# v0_4v1_0.net
KiCad netlist of a schematic drawn in EAGLE
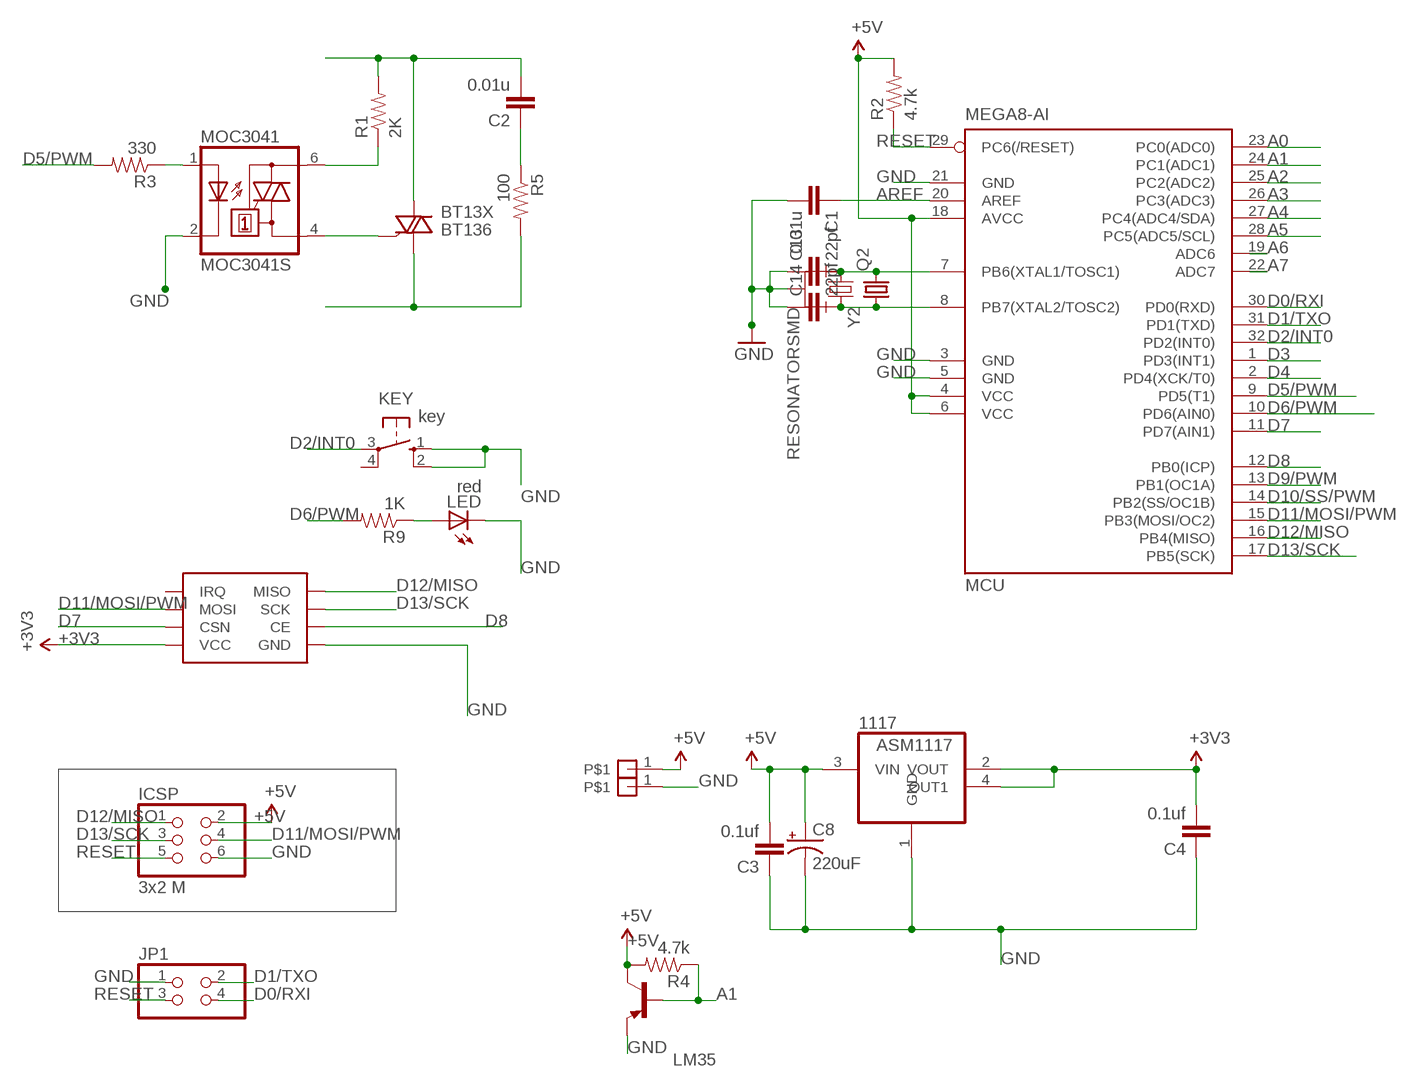
[diagram p0: schematic, sheet 1]

(export (version "E")
  (design (tool "Eeschema 10.0.6"))
  (components
    (comp (ref "1117")
      (value "ASM1117")
      (footprint "eagle-import:SOT223")
      (fields (field (name "MPN") "REG1117"))
      (libsource (lib "eagle-import") (part "ASM1117"))
    )
    (comp (ref "BT13X")
      (value "BT136")
      (footprint "eagle-import:TO252")
      (libsource (lib "eagle-import") (part "BT136"))
    )
    (comp (ref "C1")
      (value "0.01u")
      (footprint "eagle-import:0603-CAP")
      (libsource (lib "eagle-import") (part "MY2_CAP0603-CAP"))
    )
    (comp (ref "C2")
      (value "0.01u")
      (footprint "eagle-import:C050-024X044")
      (libsource (lib "eagle-import") (part "C-EU050-024X044"))
    )
    (comp (ref "C3")
      (value "0.1uf")
      (footprint "eagle-import:0603-CAP")
      (libsource (lib "eagle-import") (part "MY_CAP0603-CAP"))
    )
    (comp (ref "C4")
      (value "0.1uf")
      (footprint "eagle-import:0603-CAP")
      (libsource (lib "eagle-import") (part "MY_CAP0603-CAP"))
    )
    (comp (ref "C8")
      (value "220uF")
      (footprint "eagle-import:EIA3528")
      (libsource (lib "eagle-import") (part "CAP_POL3528"))
    )
    (comp (ref "C13")
      (value "22pf")
      (footprint "eagle-import:0603-CAP")
      (libsource (lib "eagle-import") (part "CAP0603-CAP"))
    )
    (comp (ref "C14")
      (value "22pf")
      (footprint "eagle-import:0603-CAP")
      (libsource (lib "eagle-import") (part "CAP0603-CAP"))
    )
    (comp (ref "ICSP")
      (value "3x2 M")
      (footprint "eagle-import:2X03")
      (libsource (lib "eagle-import") (part "PINHD-2X3"))
    )
    (comp (ref "JP1")
      (value "PINHD-2X2")
      (footprint "eagle-import:2X02")
      (libsource (lib "eagle-import") (part "PINHD-2X2"))
    )
    (comp (ref "KEY")
      (value "key")
      (footprint "eagle-import:B3F-10XX")
      (fields
        (field (name "MPN") "B3F-1000")
        (field (name "MPN_1") "B3F-1000")
        (field (name "OC_FARNELL") "176432")
        (field (name "OC_NEWARK") "36M3542")
      )
      (libsource (lib "eagle-import") (part "10-XX"))
    )
    (comp (ref "LED")
      (value "red")
      (footprint "eagle-import:LED3MM")
      (libsource (lib "eagle-import") (part "LED3MM"))
    )
    (comp (ref "LM35")
      (value "-PNP-TO92-E1")
      (footprint "eagle-import:TO92-E1")
      (libsource (lib "eagle-import") (part "-PNP-TO92-E1"))
    )
    (comp (ref "MCU")
      (value "MEGA8-AI")
      (footprint "eagle-import:TQFP32-08")
      (fields (field (name "MPN") "ATMEGA8-16AU"))
      (libsource (lib "eagle-import") (part "MEGA8-AI"))
    )
    (comp (ref "MOC3041")
      (value "MOC3041S")
      (footprint "eagle-import:DIL6-SMD")
      (fields
        (field (name "MF") "FAIRCHILD SEMICONDUCTOR")
        (field (name "MPN") "MOC3041S-M")
        (field (name "MF_1") "FAIRCHILD SEMICONDUCTOR")
        (field (name "MPN_1") "MOC3041S-M")
        (field (name "OC_NEWARK") "05C2885")
      )
      (libsource (lib "eagle-import") (part "MOC30S41"))
    )
    (comp (ref "Q2")
      (value "CRYSTALHC49S")
      (footprint "eagle-import:HC49_S")
      (libsource (lib "eagle-import") (part "CRYSTALHC49S"))
    )
    (comp (ref "R1")
      (value "2K")
      (footprint "eagle-import:AXIAL-0.3")
      (libsource (lib "eagle-import") (part "MY3_RESISTORPTH1"))
    )
    (comp (ref "R2")
      (value "4.7k")
      (footprint "eagle-import:0603-RES")
      (libsource (lib "eagle-import") (part "RESISTOR0603-RES"))
    )
    (comp (ref "R3")
      (value "330")
      (footprint "eagle-import:0603-RES")
      (libsource (lib "eagle-import") (part "RESISTOR0603-RES"))
    )
    (comp (ref "R4")
      (value "4.7k")
      (footprint "eagle-import:0603-RES")
      (libsource (lib "eagle-import") (part "RESISTOR0603-RES"))
    )
    (comp (ref "R5")
      (value "100")
      (footprint "eagle-import:AXIAL-0.3")
      (libsource (lib "eagle-import") (part "MY3_RESISTORPTH1"))
    )
    (comp (ref "R9")
      (value "1K")
      (footprint "eagle-import:0603-RES")
      (libsource (lib "eagle-import") (part "RESISTOR0603-RES"))
    )
    (comp (ref "U$3")
      (value "PIN1")
      (footprint "eagle-import:PIN1")
      (libsource (lib "eagle-import") (part "PIN1"))
    )
    (comp (ref "U$4")
      (value "PIN1")
      (footprint "eagle-import:PIN1")
      (libsource (lib "eagle-import") (part "PIN1"))
    )
    (comp (ref "U$6")
      (value "NRF")
      (footprint "eagle-import:NRF")
      (libsource (lib "eagle-import") (part "NRF"))
    )
    (comp (ref "Y2")
      (value "RESONATORSMD")
      (footprint "eagle-import:RESONATOR-SMD")
      (libsource (lib "eagle-import") (part "RESONATORSMD"))
    )
  )
  (nets
    (net (code "1") (name "+3V3") (class "Default")
      (node (ref "1117") (pin "2") (pinfunction "VOUT_2") (pintype "output"))
      (node (ref "1117") (pin "4") (pinfunction "OUT1_4") (pintype "bidirectional"))
      (node (ref "C4") (pin "2") (pinfunction "2_2") (pintype "passive"))
      (node (ref "U$6") (pin "P$2") (pinfunction "VCC_P$2") (pintype "bidirectional"))
    )
    (net (code "2") (name "+5V") (class "Default")
      (node (ref "1117") (pin "3") (pinfunction "VIN_3") (pintype "input"))
      (node (ref "C3") (pin "2") (pinfunction "2_2") (pintype "passive"))
      (node (ref "C8") (pin "A") (pinfunction "+_A") (pintype "passive"))
      (node (ref "ICSP") (pin "2") (pinfunction "2_2") (pintype "passive"))
      (node (ref "LM35") (pin "1") (pinfunction "C_1") (pintype "passive"))
      (node (ref "MCU") (pin "18") (pinfunction "AVCC_18") (pintype "power_in"))
      (node (ref "MCU") (pin "4") (pinfunction "VCC_4") (pintype "power_in"))
      (node (ref "MCU") (pin "6") (pinfunction "VCC_6") (pintype "power_in"))
      (node (ref "R2") (pin "2") (pinfunction "2_2") (pintype "passive"))
      (node (ref "R4") (pin "2") (pinfunction "2_2") (pintype "passive"))
      (node (ref "U$3") (pin "1") (pinfunction "P$1_1") (pintype "bidirectional"))
    )
    (net (code "3") (name "/A0") (class "Default")
      (node (ref "MCU") (pin "23") (pinfunction "PC0(ADC0)_23") (pintype "bidirectional"))
    )
    (net (code "4") (name "/A1") (class "Default")
      (node (ref "LM35") (pin "2") (pinfunction "B_2") (pintype "passive"))
      (node (ref "MCU") (pin "24") (pinfunction "PC1(ADC1)_24") (pintype "bidirectional"))
      (node (ref "R4") (pin "1") (pinfunction "1_1") (pintype "passive"))
    )
    (net (code "5") (name "/A2") (class "Default")
      (node (ref "MCU") (pin "25") (pinfunction "PC2(ADC2)_25") (pintype "bidirectional"))
    )
    (net (code "6") (name "/A3") (class "Default")
      (node (ref "MCU") (pin "26") (pinfunction "PC3(ADC3)_26") (pintype "bidirectional"))
    )
    (net (code "7") (name "/A4") (class "Default")
      (node (ref "MCU") (pin "27") (pinfunction "PC4(ADC4/SDA)_27") (pintype "bidirectional"))
    )
    (net (code "8") (name "/A5") (class "Default")
      (node (ref "MCU") (pin "28") (pinfunction "PC5(ADC5/SCL)_28") (pintype "bidirectional"))
    )
    (net (code "9") (name "/A6") (class "Default")
      (node (ref "MCU") (pin "19") (pinfunction "ADC6_19") (pintype "bidirectional"))
    )
    (net (code "10") (name "/A7") (class "Default")
      (node (ref "MCU") (pin "22") (pinfunction "ADC7_22") (pintype "bidirectional"))
    )
    (net (code "11") (name "/AREF") (class "Default")
      (node (ref "C1") (pin "1") (pinfunction "1_1") (pintype "passive"))
      (node (ref "MCU") (pin "20") (pinfunction "AREF_20") (pintype "passive"))
    )
    (net (code "12") (name "/D0{slash}RXI") (class "Default")
      (node (ref "JP1") (pin "4") (pinfunction "4_4") (pintype "passive"))
      (node (ref "MCU") (pin "30") (pinfunction "PD0(RXD)_30") (pintype "bidirectional"))
    )
    (net (code "13") (name "/D1{slash}TXO") (class "Default")
      (node (ref "JP1") (pin "2") (pinfunction "2_2") (pintype "passive"))
      (node (ref "MCU") (pin "31") (pinfunction "PD1(TXD)_31") (pintype "bidirectional"))
    )
    (net (code "14") (name "/D2{slash}INT0") (class "Default")
      (node (ref "KEY") (pin "3") (pinfunction "P_3") (pintype "passive"))
      (node (ref "MCU") (pin "32") (pinfunction "PD2(INT0)_32") (pintype "bidirectional"))
    )
    (net (code "15") (name "/D3") (class "Default")
      (node (ref "MCU") (pin "1") (pinfunction "PD3(INT1)_1") (pintype "bidirectional"))
    )
    (net (code "16") (name "/D4") (class "Default")
      (node (ref "MCU") (pin "2") (pinfunction "PD4(XCK/T0)_2") (pintype "bidirectional"))
    )
    (net (code "17") (name "/D5{slash}PWM") (class "Default")
      (node (ref "MCU") (pin "9") (pinfunction "PD5(T1)_9") (pintype "bidirectional"))
      (node (ref "R3") (pin "2") (pinfunction "2_2") (pintype "passive"))
    )
    (net (code "18") (name "/D6{slash}PWM") (class "Default")
      (node (ref "MCU") (pin "10") (pinfunction "PD6(AIN0)_10") (pintype "bidirectional"))
      (node (ref "R9") (pin "2") (pinfunction "2_2") (pintype "passive"))
    )
    (net (code "19") (name "/D7") (class "Default")
      (node (ref "MCU") (pin "11") (pinfunction "PD7(AIN1)_11") (pintype "bidirectional"))
      (node (ref "U$6") (pin "P$4") (pinfunction "CSN_P$4") (pintype "bidirectional"))
    )
    (net (code "20") (name "/D8") (class "Default")
      (node (ref "MCU") (pin "12") (pinfunction "PB0(ICP)_12") (pintype "bidirectional"))
      (node (ref "U$6") (pin "P$3") (pinfunction "CE_P$3") (pintype "bidirectional"))
    )
    (net (code "21") (name "/D9{slash}PWM") (class "Default")
      (node (ref "MCU") (pin "13") (pinfunction "PB1(OC1A)_13") (pintype "bidirectional"))
    )
    (net (code "22") (name "/D10{slash}SS{slash}PWM") (class "Default")
      (node (ref "MCU") (pin "14") (pinfunction "PB2(SS/OC1B)_14") (pintype "bidirectional"))
    )
    (net (code "23") (name "/D11{slash}MOSI{slash}PWM") (class "Default")
      (node (ref "ICSP") (pin "4") (pinfunction "4_4") (pintype "passive"))
      (node (ref "MCU") (pin "15") (pinfunction "PB3(MOSI/OC2)_15") (pintype "bidirectional"))
      (node (ref "U$6") (pin "P$6") (pinfunction "MOSI_P$6") (pintype "bidirectional"))
    )
    (net (code "24") (name "/D12{slash}MISO") (class "Default")
      (node (ref "ICSP") (pin "1") (pinfunction "1_1") (pintype "passive"))
      (node (ref "MCU") (pin "16") (pinfunction "PB4(MISO)_16") (pintype "bidirectional"))
      (node (ref "U$6") (pin "P$7") (pinfunction "MISO_P$7") (pintype "bidirectional"))
    )
    (net (code "25") (name "/D13{slash}SCK") (class "Default")
      (node (ref "ICSP") (pin "3") (pinfunction "3_3") (pintype "passive"))
      (node (ref "MCU") (pin "17") (pinfunction "PB5(SCK)_17") (pintype "bidirectional"))
      (node (ref "U$6") (pin "P$5") (pinfunction "SCK_P$5") (pintype "bidirectional"))
    )
    (net (code "26") (name "/RESET") (class "Default")
      (node (ref "ICSP") (pin "5") (pinfunction "5_5") (pintype "passive"))
      (node (ref "JP1") (pin "3") (pinfunction "3_3") (pintype "passive"))
      (node (ref "MCU") (pin "29") (pinfunction "PC6(/RESET)_29") (pintype "bidirectional"))
      (node (ref "R2") (pin "1") (pinfunction "1_1") (pintype "passive"))
    )
    (net (code "27") (name "GND") (class "Default")
      (node (ref "1117") (pin "1") (pinfunction "GND_1") (pintype "power_in"))
      (node (ref "C1") (pin "2") (pinfunction "2_2") (pintype "passive"))
      (node (ref "C13") (pin "1") (pinfunction "1_1") (pintype "passive"))
      (node (ref "C14") (pin "1") (pinfunction "1_1") (pintype "passive"))
      (node (ref "C3") (pin "1") (pinfunction "1_1") (pintype "passive"))
      (node (ref "C4") (pin "1") (pinfunction "1_1") (pintype "passive"))
      (node (ref "C8") (pin "C") (pinfunction "-_C") (pintype "passive"))
      (node (ref "ICSP") (pin "6") (pinfunction "6_6") (pintype "passive"))
      (node (ref "JP1") (pin "1") (pinfunction "1_1") (pintype "passive"))
      (node (ref "KEY") (pin "1") (pinfunction "S_1") (pintype "passive"))
      (node (ref "KEY") (pin "2") (pinfunction "S1_2") (pintype "passive"))
      (node (ref "LED") (pin "K") (pinfunction "C_K") (pintype "passive"))
      (node (ref "LM35") (pin "3") (pinfunction "E_3") (pintype "passive"))
      (node (ref "MCU") (pin "21") (pinfunction "GND_21") (pintype "power_in"))
      (node (ref "MCU") (pin "3") (pinfunction "GND_3") (pintype "power_in"))
      (node (ref "MCU") (pin "5") (pinfunction "GND_5") (pintype "power_in"))
      (node (ref "MOC3041") (pin "2") (pinfunction "C_2") (pintype "passive"))
      (node (ref "U$4") (pin "1") (pinfunction "P$1_1") (pintype "bidirectional"))
      (node (ref "U$6") (pin "P$1") (pinfunction "GND_P$1") (pintype "bidirectional"))
      (node (ref "Y2") (pin "2") (pinfunction "2_2") (pintype "passive"))
    )
    (net (code "28") (name "Net-(BT13X-A1)") (class "Default")
      (node (ref "BT13X") (pin "1") (pinfunction "A1_1") (pintype "passive"))
      (node (ref "R5") (pin "P$2") (pinfunction "2_P$2") (pintype "passive"))
    )
    (net (code "29") (name "Net-(BT13X-A2)") (class "Default")
      (node (ref "BT13X") (pin "3") (pinfunction "A2_3") (pintype "passive"))
      (node (ref "C2") (pin "2") (pinfunction "2_2") (pintype "passive"))
      (node (ref "R1") (pin "P$2") (pinfunction "2_P$2") (pintype "passive"))
    )
    (net (code "30") (name "Net-(BT13X-G)") (class "Default")
      (node (ref "BT13X") (pin "2") (pinfunction "G_2") (pintype "passive"))
      (node (ref "MOC3041") (pin "4") (pinfunction "A1_4") (pintype "passive"))
    )
    (net (code "31") (name "Net-(LED-PadA)") (class "Default")
      (node (ref "LED") (pin "A") (pinfunction "A_A") (pintype "passive"))
      (node (ref "R9") (pin "1") (pinfunction "1_1") (pintype "passive"))
    )
    (net (code "32") (name "Net-(MCU-PB6(XTAL1{slash}TOSC1))") (class "Default")
      (node (ref "C13") (pin "2") (pinfunction "2_2") (pintype "passive"))
      (node (ref "MCU") (pin "7") (pinfunction "PB6(XTAL1/TOSC1)_7") (pintype "bidirectional"))
      (node (ref "Q2") (pin "2") (pinfunction "2_2") (pintype "passive"))
      (node (ref "Y2") (pin "1") (pinfunction "1_1") (pintype "passive"))
    )
    (net (code "33") (name "Net-(MCU-PB7(XTAL2{slash}TOSC2))") (class "Default")
      (node (ref "C14") (pin "2") (pinfunction "2_2") (pintype "passive"))
      (node (ref "MCU") (pin "8") (pinfunction "PB7(XTAL2/TOSC2)_8") (pintype "bidirectional"))
      (node (ref "Q2") (pin "1") (pinfunction "1_1") (pintype "passive"))
      (node (ref "Y2") (pin "3") (pinfunction "3_3") (pintype "passive"))
    )
    (net (code "34") (name "Net-(MOC3041-A)") (class "Default")
      (node (ref "MOC3041") (pin "1") (pinfunction "A_1") (pintype "passive"))
      (node (ref "R3") (pin "1") (pinfunction "1_1") (pintype "passive"))
    )
    (net (code "35") (name "Net-(MOC3041-A2)") (class "Default")
      (node (ref "MOC3041") (pin "6") (pinfunction "A2_6") (pintype "passive"))
      (node (ref "R1") (pin "P$1") (pinfunction "1_P$1") (pintype "passive"))
    )
    (net (code "36") (name "Net-(R5-1)") (class "Default")
      (node (ref "C2") (pin "1") (pinfunction "1_1") (pintype "passive"))
      (node (ref "R5") (pin "P$1") (pinfunction "1_P$1") (pintype "passive"))
    )
    (net (code "37") (name "unconnected-(KEY-P1-Pad4)") (class "Default")
      (node (ref "KEY") (pin "4") (pinfunction "P1_4") (pintype "passive"))
    )
    (net (code "38") (name "unconnected-(U$6-IRQ-PadP$8)") (class "Default")
      (node (ref "U$6") (pin "P$8") (pinfunction "IRQ_P$8") (pintype "bidirectional"))
    )
  )
)
